# CLAVIER_MIDI_WOOD_2021-01-15.net
KiCad netlist of a schematic drawn in EasyEDA
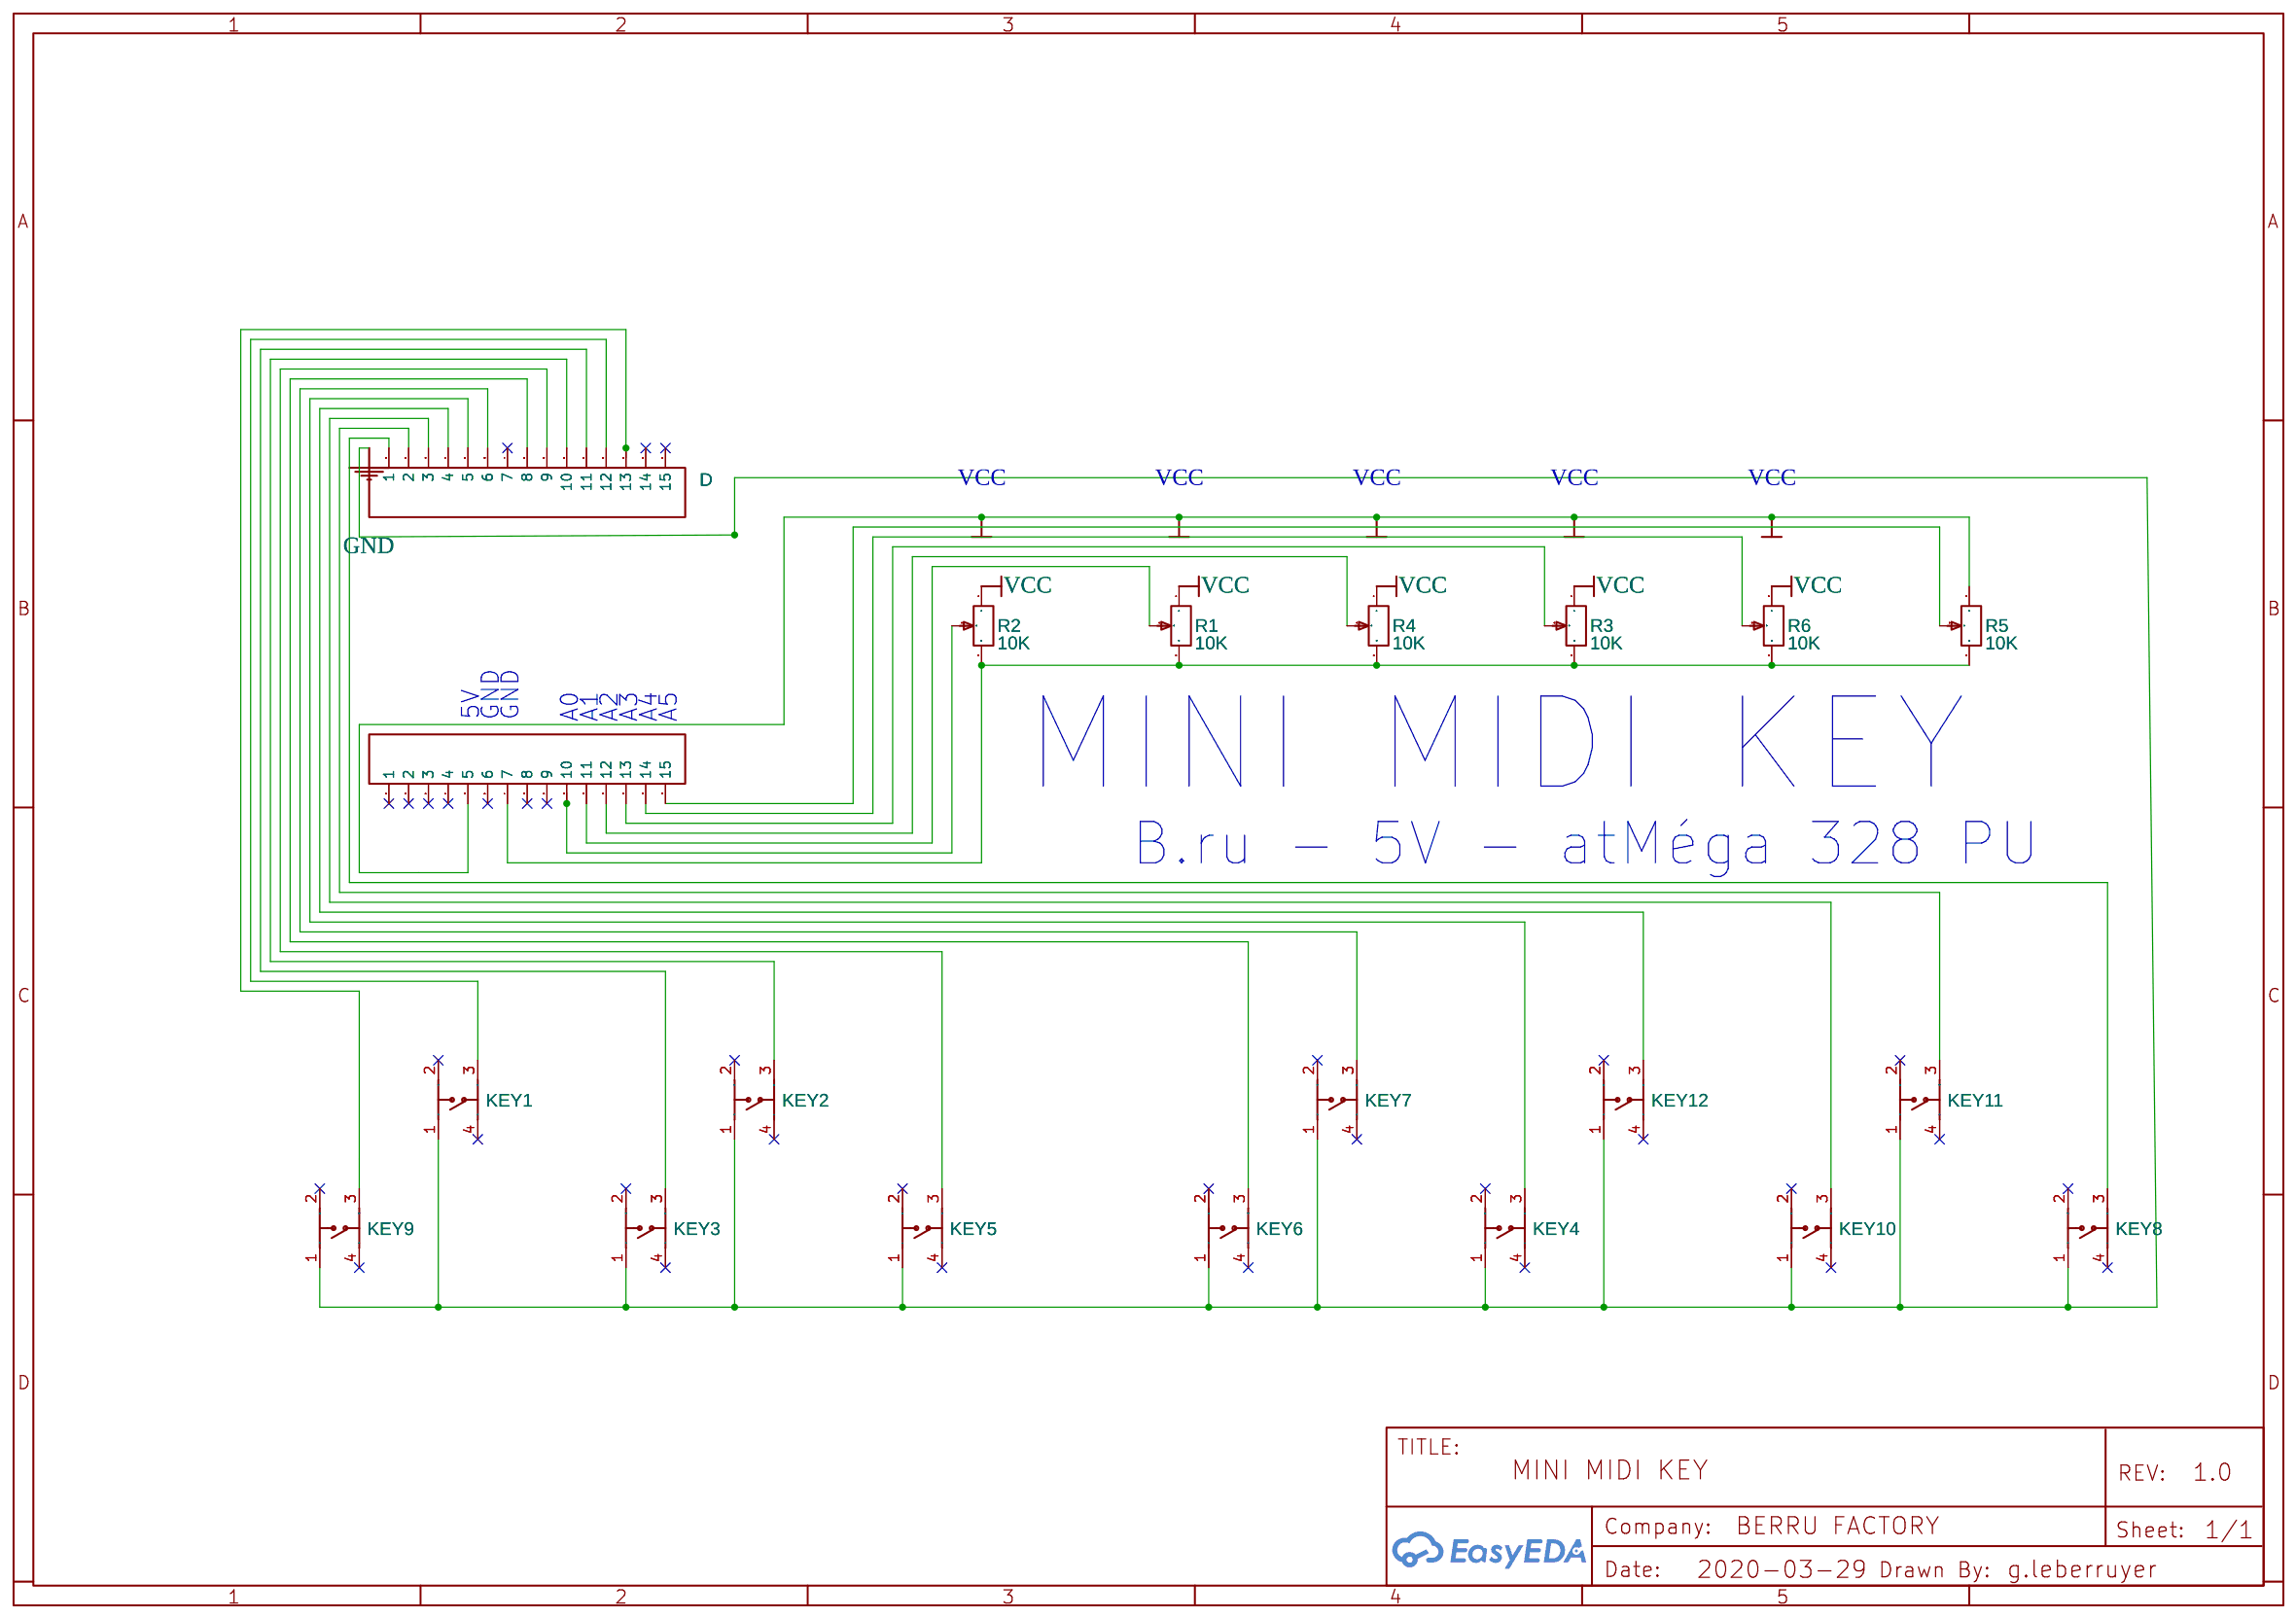
[diagram p0: schematic sheet]

(export (version "E")
  (design (tool "Eeschema 10.0.6"))
  (components
    (comp (ref "D")
      (value "Header-Female-2.54_1x15")
      (fields
        (field (name "BOM_Manufacturer Part") "220S-1*15P H=8.5MM Ytype Gold-plated")
        (field (name "BOM_Supplier Part") "C124408")
      )
      (libsource (lib "") (part "Header-Female-2.54_1x15"))
    )
    (comp (ref "H1")
      (value "Header-Female-2.54_1x15")
      (fields
        (field (name "BOM_Manufacturer Part") "220S-1*15P H=8.5MM Ytype Gold-plated")
        (field (name "BOM_Supplier Part") "C124408")
      )
      (libsource (lib "") (part "Header-Female-2.54_1x15_1"))
    )
    (comp (ref "KEY1")
      (value "button6*6*8")
      (fields (field (name "BOM_Supplier Part") "C59982"))
      (libsource (lib "") (part "button6*6*8"))
    )
    (comp (ref "KEY2")
      (value "button6*6*8")
      (fields (field (name "BOM_Supplier Part") "C59982"))
      (libsource (lib "") (part "button6*6*8"))
    )
    (comp (ref "KEY3")
      (value "button6*6*8")
      (fields (field (name "BOM_Supplier Part") "C59982"))
      (libsource (lib "") (part "button6*6*8"))
    )
    (comp (ref "KEY4")
      (value "button6*6*8")
      (fields (field (name "BOM_Supplier Part") "C59982"))
      (libsource (lib "") (part "button6*6*8"))
    )
    (comp (ref "KEY5")
      (value "button6*6*8")
      (fields (field (name "BOM_Supplier Part") "C59982"))
      (libsource (lib "") (part "button6*6*8"))
    )
    (comp (ref "KEY6")
      (value "button6*6*8")
      (fields (field (name "BOM_Supplier Part") "C59982"))
      (libsource (lib "") (part "button6*6*8"))
    )
    (comp (ref "KEY7")
      (value "button6*6*8")
      (fields (field (name "BOM_Supplier Part") "C59982"))
      (libsource (lib "") (part "button6*6*8"))
    )
    (comp (ref "KEY8")
      (value "button6*6*8")
      (fields (field (name "BOM_Supplier Part") "C59982"))
      (libsource (lib "") (part "button6*6*8"))
    )
    (comp (ref "KEY9")
      (value "button6*6*8")
      (fields (field (name "BOM_Supplier Part") "C59982"))
      (libsource (lib "") (part "button6*6*8"))
    )
    (comp (ref "KEY10")
      (value "button6*6*8")
      (fields (field (name "BOM_Supplier Part") "C59982"))
      (libsource (lib "") (part "button6*6*8"))
    )
    (comp (ref "KEY11")
      (value "button6*6*8")
      (fields (field (name "BOM_Supplier Part") "C59982"))
      (libsource (lib "") (part "button6*6*8"))
    )
    (comp (ref "KEY12")
      (value "button6*6*8")
      (fields (field (name "BOM_Supplier Part") "C59982"))
      (libsource (lib "") (part "button6*6*8"))
    )
    (comp (ref "R1")
      (value "10K")
      (fields
        (field (name "BOM_Manufacturer Part") "RK097111080J")
        (field (name "BOM_Supplier Part") "C97444")
      )
      (libsource (lib "") (part "RK097111080J"))
    )
    (comp (ref "R2")
      (value "10K")
      (fields
        (field (name "BOM_Manufacturer Part") "RK097111080J")
        (field (name "BOM_Supplier Part") "C97444")
      )
      (libsource (lib "") (part "RK097111080J"))
    )
    (comp (ref "R3")
      (value "10K")
      (fields
        (field (name "BOM_Manufacturer Part") "RK097111080J")
        (field (name "BOM_Supplier Part") "C97444")
      )
      (libsource (lib "") (part "RK097111080J"))
    )
    (comp (ref "R4")
      (value "10K")
      (fields
        (field (name "BOM_Manufacturer Part") "RK097111080J")
        (field (name "BOM_Supplier Part") "C97444")
      )
      (libsource (lib "") (part "RK097111080J"))
    )
    (comp (ref "R5")
      (value "10K")
      (fields
        (field (name "BOM_Manufacturer Part") "RK097111080J")
        (field (name "BOM_Supplier Part") "C97444")
      )
      (libsource (lib "") (part "RK097111080J"))
    )
    (comp (ref "R6")
      (value "10K")
      (fields
        (field (name "BOM_Manufacturer Part") "RK097111080J")
        (field (name "BOM_Supplier Part") "C97444")
      )
      (libsource (lib "") (part "RK097111080J"))
    )
  )
  (nets
    (net (code "1") (name "GND") (class "Default")
      (node (ref "KEY1") (pin "1") (pinfunction "1_1") (pintype "unspecified"))
      (node (ref "KEY10") (pin "1") (pinfunction "1_1") (pintype "unspecified"))
      (node (ref "KEY11") (pin "1") (pinfunction "1_1") (pintype "unspecified"))
      (node (ref "KEY12") (pin "1") (pinfunction "1_1") (pintype "unspecified"))
      (node (ref "KEY2") (pin "1") (pinfunction "1_1") (pintype "unspecified"))
      (node (ref "KEY3") (pin "1") (pinfunction "1_1") (pintype "unspecified"))
      (node (ref "KEY4") (pin "1") (pinfunction "1_1") (pintype "unspecified"))
      (node (ref "KEY5") (pin "1") (pinfunction "1_1") (pintype "unspecified"))
      (node (ref "KEY6") (pin "1") (pinfunction "1_1") (pintype "unspecified"))
      (node (ref "KEY7") (pin "1") (pinfunction "1_1") (pintype "unspecified"))
      (node (ref "KEY8") (pin "1") (pinfunction "1_1") (pintype "unspecified"))
      (node (ref "KEY9") (pin "1") (pinfunction "1_1") (pintype "unspecified"))
    )
    (net (code "2") (name "Net-(D-Pad1)") (class "Default")
      (node (ref "D") (pin "1") (pinfunction "1_1") (pintype "unspecified"))
      (node (ref "KEY8") (pin "3") (pinfunction "3_3") (pintype "unspecified"))
    )
    (net (code "3") (name "Net-(D-Pad2)") (class "Default")
      (node (ref "D") (pin "2") (pinfunction "2_2") (pintype "unspecified"))
      (node (ref "KEY11") (pin "3") (pinfunction "3_3") (pintype "unspecified"))
    )
    (net (code "4") (name "Net-(D-Pad3)") (class "Default")
      (node (ref "D") (pin "3") (pinfunction "3_3") (pintype "unspecified"))
      (node (ref "KEY10") (pin "3") (pinfunction "3_3") (pintype "unspecified"))
    )
    (net (code "5") (name "Net-(D-Pad4)") (class "Default")
      (node (ref "D") (pin "4") (pinfunction "4_4") (pintype "unspecified"))
      (node (ref "KEY12") (pin "3") (pinfunction "3_3") (pintype "unspecified"))
    )
    (net (code "6") (name "Net-(D-Pad5)") (class "Default")
      (node (ref "D") (pin "5") (pinfunction "5_5") (pintype "unspecified"))
      (node (ref "KEY4") (pin "3") (pinfunction "3_3") (pintype "unspecified"))
    )
    (net (code "7") (name "Net-(D-Pad6)") (class "Default")
      (node (ref "D") (pin "6") (pinfunction "6_6") (pintype "unspecified"))
      (node (ref "KEY7") (pin "3") (pinfunction "3_3") (pintype "unspecified"))
    )
    (net (code "8") (name "Net-(D-Pad8)") (class "Default")
      (node (ref "D") (pin "8") (pinfunction "8_8") (pintype "unspecified"))
      (node (ref "KEY6") (pin "3") (pinfunction "3_3") (pintype "unspecified"))
    )
    (net (code "9") (name "Net-(D-Pad9)") (class "Default")
      (node (ref "D") (pin "9") (pinfunction "9_9") (pintype "unspecified"))
      (node (ref "KEY5") (pin "3") (pinfunction "3_3") (pintype "unspecified"))
    )
    (net (code "10") (name "Net-(D-Pad10)") (class "Default")
      (node (ref "D") (pin "10") (pinfunction "10_10") (pintype "unspecified"))
      (node (ref "KEY2") (pin "3") (pinfunction "3_3") (pintype "unspecified"))
    )
    (net (code "11") (name "Net-(D-Pad11)") (class "Default")
      (node (ref "D") (pin "11") (pinfunction "11_11") (pintype "unspecified"))
      (node (ref "KEY3") (pin "3") (pinfunction "3_3") (pintype "unspecified"))
    )
    (net (code "12") (name "Net-(D-Pad12)") (class "Default")
      (node (ref "D") (pin "12") (pinfunction "12_12") (pintype "unspecified"))
      (node (ref "KEY1") (pin "3") (pinfunction "3_3") (pintype "unspecified"))
    )
    (net (code "13") (name "Net-(D-Pad13)") (class "Default")
      (node (ref "D") (pin "13") (pinfunction "13_13") (pintype "unspecified"))
      (node (ref "KEY9") (pin "3") (pinfunction "3_3") (pintype "unspecified"))
    )
    (net (code "14") (name "Net-(H1-Pad7)") (class "Default")
      (node (ref "H1") (pin "7") (pinfunction "7_7") (pintype "unspecified"))
      (node (ref "R1") (pin "3") (pinfunction "3_3") (pintype "input"))
      (node (ref "R2") (pin "3") (pinfunction "3_3") (pintype "input"))
      (node (ref "R3") (pin "3") (pinfunction "3_3") (pintype "input"))
      (node (ref "R4") (pin "3") (pinfunction "3_3") (pintype "input"))
      (node (ref "R5") (pin "3") (pinfunction "3_3") (pintype "input"))
      (node (ref "R6") (pin "3") (pinfunction "3_3") (pintype "input"))
    )
    (net (code "15") (name "Net-(H1-Pad10)") (class "Default")
      (node (ref "H1") (pin "10") (pinfunction "10_10") (pintype "unspecified"))
      (node (ref "R2") (pin "2") (pinfunction "2_2") (pintype "input"))
    )
    (net (code "16") (name "Net-(H1-Pad11)") (class "Default")
      (node (ref "H1") (pin "11") (pinfunction "11_11") (pintype "unspecified"))
      (node (ref "R1") (pin "2") (pinfunction "2_2") (pintype "input"))
    )
    (net (code "17") (name "Net-(H1-Pad12)") (class "Default")
      (node (ref "H1") (pin "12") (pinfunction "12_12") (pintype "unspecified"))
      (node (ref "R4") (pin "2") (pinfunction "2_2") (pintype "input"))
    )
    (net (code "18") (name "Net-(H1-Pad13)") (class "Default")
      (node (ref "H1") (pin "13") (pinfunction "13_13") (pintype "unspecified"))
      (node (ref "R3") (pin "2") (pinfunction "2_2") (pintype "input"))
    )
    (net (code "19") (name "Net-(H1-Pad14)") (class "Default")
      (node (ref "H1") (pin "14") (pinfunction "14_14") (pintype "unspecified"))
      (node (ref "R6") (pin "2") (pinfunction "2_2") (pintype "input"))
    )
    (net (code "20") (name "Net-(H1-Pad15)") (class "Default")
      (node (ref "H1") (pin "15") (pinfunction "15_15") (pintype "unspecified"))
      (node (ref "R5") (pin "2") (pinfunction "2_2") (pintype "input"))
    )
    (net (code "21") (name "VCC") (class "Default")
      (node (ref "H1") (pin "5") (pinfunction "5_5") (pintype "unspecified"))
      (node (ref "R1") (pin "1") (pinfunction "1_1") (pintype "input"))
      (node (ref "R2") (pin "1") (pinfunction "1_1") (pintype "input"))
      (node (ref "R3") (pin "1") (pinfunction "1_1") (pintype "input"))
      (node (ref "R4") (pin "1") (pinfunction "1_1") (pintype "input"))
      (node (ref "R5") (pin "1") (pinfunction "1_1") (pintype "input"))
      (node (ref "R6") (pin "1") (pinfunction "1_1") (pintype "input"))
    )
    (net (code "22") (name "unconnected-(D-Pad7)") (class "Default")
      (node (ref "D") (pin "7") (pinfunction "7_7") (pintype "unspecified+no_connect"))
    )
    (net (code "23") (name "unconnected-(D-Pad14)") (class "Default")
      (node (ref "D") (pin "14") (pinfunction "14_14") (pintype "unspecified+no_connect"))
    )
    (net (code "24") (name "unconnected-(D-Pad15)") (class "Default")
      (node (ref "D") (pin "15") (pinfunction "15_15") (pintype "unspecified+no_connect"))
    )
    (net (code "25") (name "unconnected-(H1-Pad1)") (class "Default")
      (node (ref "H1") (pin "1") (pinfunction "1_1") (pintype "unspecified+no_connect"))
    )
    (net (code "26") (name "unconnected-(H1-Pad2)") (class "Default")
      (node (ref "H1") (pin "2") (pinfunction "2_2") (pintype "unspecified+no_connect"))
    )
    (net (code "27") (name "unconnected-(H1-Pad3)") (class "Default")
      (node (ref "H1") (pin "3") (pinfunction "3_3") (pintype "unspecified+no_connect"))
    )
    (net (code "28") (name "unconnected-(H1-Pad4)") (class "Default")
      (node (ref "H1") (pin "4") (pinfunction "4_4") (pintype "unspecified+no_connect"))
    )
    (net (code "29") (name "unconnected-(H1-Pad6)") (class "Default")
      (node (ref "H1") (pin "6") (pinfunction "6_6") (pintype "unspecified+no_connect"))
    )
    (net (code "30") (name "unconnected-(H1-Pad8)") (class "Default")
      (node (ref "H1") (pin "8") (pinfunction "8_8") (pintype "unspecified+no_connect"))
    )
    (net (code "31") (name "unconnected-(H1-Pad9)") (class "Default")
      (node (ref "H1") (pin "9") (pinfunction "9_9") (pintype "unspecified+no_connect"))
    )
    (net (code "32") (name "unconnected-(KEY1-Pad2)") (class "Default")
      (node (ref "KEY1") (pin "2") (pinfunction "2_2") (pintype "unspecified+no_connect"))
    )
    (net (code "33") (name "unconnected-(KEY1-Pad4)") (class "Default")
      (node (ref "KEY1") (pin "4") (pinfunction "4_4") (pintype "unspecified+no_connect"))
    )
    (net (code "34") (name "unconnected-(KEY2-Pad2)") (class "Default")
      (node (ref "KEY2") (pin "2") (pinfunction "2_2") (pintype "unspecified+no_connect"))
    )
    (net (code "35") (name "unconnected-(KEY2-Pad4)") (class "Default")
      (node (ref "KEY2") (pin "4") (pinfunction "4_4") (pintype "unspecified+no_connect"))
    )
    (net (code "36") (name "unconnected-(KEY3-Pad2)") (class "Default")
      (node (ref "KEY3") (pin "2") (pinfunction "2_2") (pintype "unspecified+no_connect"))
    )
    (net (code "37") (name "unconnected-(KEY3-Pad4)") (class "Default")
      (node (ref "KEY3") (pin "4") (pinfunction "4_4") (pintype "unspecified+no_connect"))
    )
    (net (code "38") (name "unconnected-(KEY4-Pad2)") (class "Default")
      (node (ref "KEY4") (pin "2") (pinfunction "2_2") (pintype "unspecified+no_connect"))
    )
    (net (code "39") (name "unconnected-(KEY4-Pad4)") (class "Default")
      (node (ref "KEY4") (pin "4") (pinfunction "4_4") (pintype "unspecified+no_connect"))
    )
    (net (code "40") (name "unconnected-(KEY5-Pad2)") (class "Default")
      (node (ref "KEY5") (pin "2") (pinfunction "2_2") (pintype "unspecified+no_connect"))
    )
    (net (code "41") (name "unconnected-(KEY5-Pad4)") (class "Default")
      (node (ref "KEY5") (pin "4") (pinfunction "4_4") (pintype "unspecified+no_connect"))
    )
    (net (code "42") (name "unconnected-(KEY6-Pad2)") (class "Default")
      (node (ref "KEY6") (pin "2") (pinfunction "2_2") (pintype "unspecified+no_connect"))
    )
    (net (code "43") (name "unconnected-(KEY6-Pad4)") (class "Default")
      (node (ref "KEY6") (pin "4") (pinfunction "4_4") (pintype "unspecified+no_connect"))
    )
    (net (code "44") (name "unconnected-(KEY7-Pad2)") (class "Default")
      (node (ref "KEY7") (pin "2") (pinfunction "2_2") (pintype "unspecified+no_connect"))
    )
    (net (code "45") (name "unconnected-(KEY7-Pad4)") (class "Default")
      (node (ref "KEY7") (pin "4") (pinfunction "4_4") (pintype "unspecified+no_connect"))
    )
    (net (code "46") (name "unconnected-(KEY8-Pad2)") (class "Default")
      (node (ref "KEY8") (pin "2") (pinfunction "2_2") (pintype "unspecified+no_connect"))
    )
    (net (code "47") (name "unconnected-(KEY8-Pad4)") (class "Default")
      (node (ref "KEY8") (pin "4") (pinfunction "4_4") (pintype "unspecified+no_connect"))
    )
    (net (code "48") (name "unconnected-(KEY9-Pad2)") (class "Default")
      (node (ref "KEY9") (pin "2") (pinfunction "2_2") (pintype "unspecified+no_connect"))
    )
    (net (code "49") (name "unconnected-(KEY9-Pad4)") (class "Default")
      (node (ref "KEY9") (pin "4") (pinfunction "4_4") (pintype "unspecified+no_connect"))
    )
    (net (code "50") (name "unconnected-(KEY10-Pad2)") (class "Default")
      (node (ref "KEY10") (pin "2") (pinfunction "2_2") (pintype "unspecified+no_connect"))
    )
    (net (code "51") (name "unconnected-(KEY10-Pad4)") (class "Default")
      (node (ref "KEY10") (pin "4") (pinfunction "4_4") (pintype "unspecified+no_connect"))
    )
    (net (code "52") (name "unconnected-(KEY11-Pad2)") (class "Default")
      (node (ref "KEY11") (pin "2") (pinfunction "2_2") (pintype "unspecified+no_connect"))
    )
    (net (code "53") (name "unconnected-(KEY11-Pad4)") (class "Default")
      (node (ref "KEY11") (pin "4") (pinfunction "4_4") (pintype "unspecified+no_connect"))
    )
    (net (code "54") (name "unconnected-(KEY12-Pad2)") (class "Default")
      (node (ref "KEY12") (pin "2") (pinfunction "2_2") (pintype "unspecified+no_connect"))
    )
    (net (code "55") (name "unconnected-(KEY12-Pad4)") (class "Default")
      (node (ref "KEY12") (pin "4") (pinfunction "4_4") (pintype "unspecified+no_connect"))
    )
  )
)
